# main.net
KiCad netlist of a schematic drawn in EAGLE
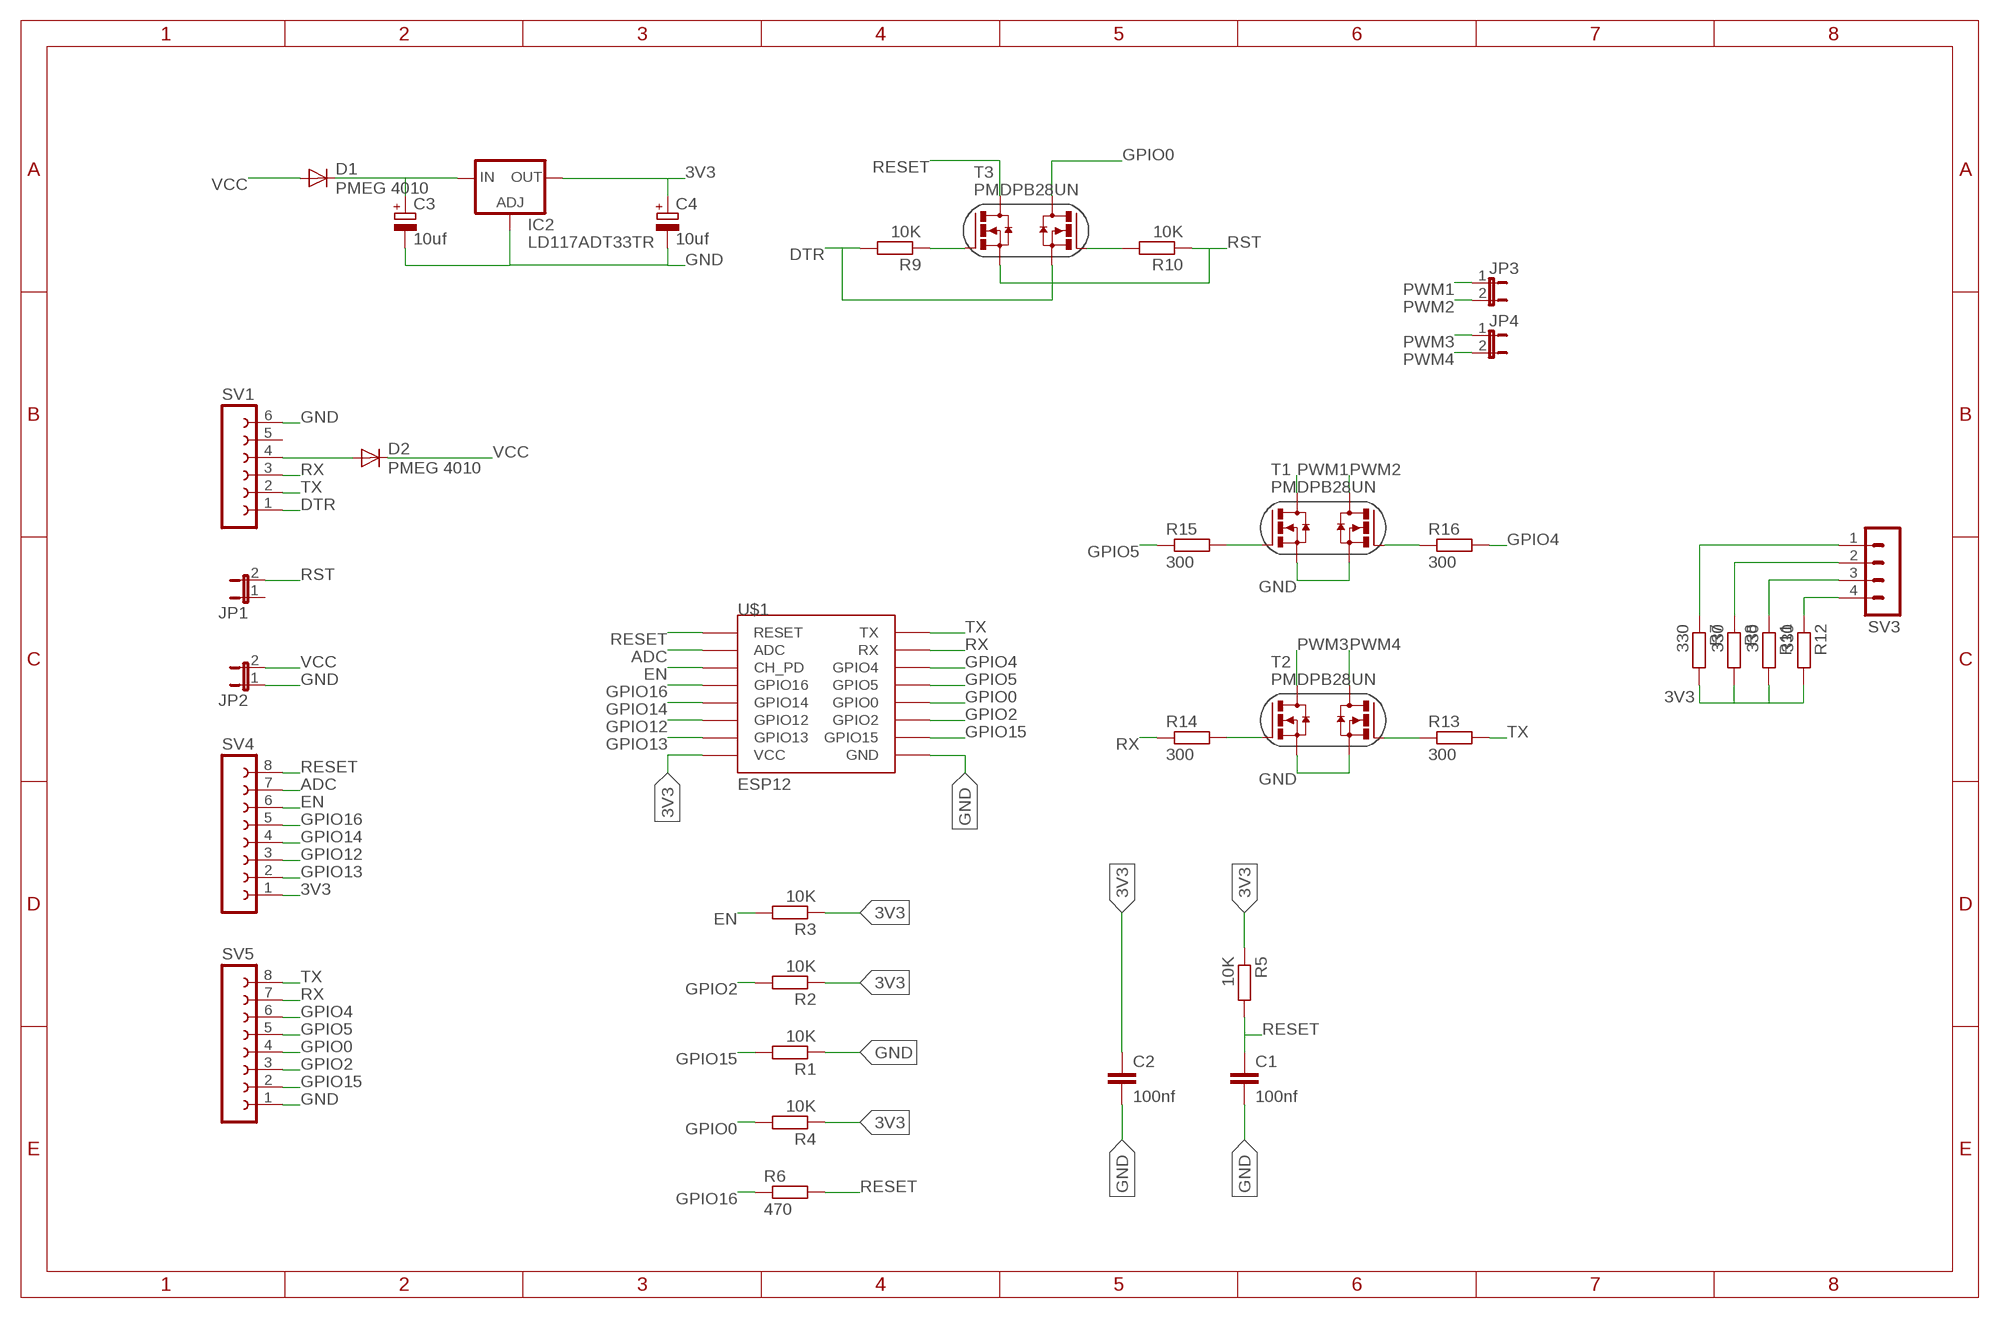
[diagram p0: schematic, sheet 1]

(export (version "E")
  (design (tool "Eeschema 10.0.6"))
  (components
    (comp (ref "C1")
      (value "100nf")
      (footprint "eagle-import:C0805K")
      (libsource (lib "eagle-import") (part "C-EUC0805K"))
    )
    (comp (ref "C2")
      (value "100nf")
      (footprint "eagle-import:C0805K")
      (libsource (lib "eagle-import") (part "C-EUC0805K"))
    )
    (comp (ref "C3")
      (value "10uf")
      (footprint "eagle-import:SMC_B")
      (libsource (lib "eagle-import") (part "CPOL-EUSMCB"))
    )
    (comp (ref "C4")
      (value "10uf")
      (footprint "eagle-import:SMC_B")
      (libsource (lib "eagle-import") (part "CPOL-EUSMCB"))
    )
    (comp (ref "D1")
      (value "PMEG 4010")
      (footprint "eagle-import:SOD-323")
      (libsource (lib "eagle-import") (part "DIODESOD"))
    )
    (comp (ref "D2")
      (value "PMEG 4010")
      (footprint "eagle-import:SOD-323")
      (libsource (lib "eagle-import") (part "DIODESOD"))
    )
    (comp (ref "IC2")
      (value "LD117ADT33TR")
      (footprint "eagle-import:DPACK")
      (libsource (lib "eagle-import") (part "LD117A?DT33TR"))
    )
    (comp (ref "JP1")
      (value "JUMPER-2PTH")
      (footprint "eagle-import:1X02")
      (libsource (lib "eagle-import") (part "JUMPER-2PTH"))
    )
    (comp (ref "JP2")
      (value "JUMPER-2PTH")
      (footprint "eagle-import:1X02")
      (libsource (lib "eagle-import") (part "JUMPER-2PTH"))
    )
    (comp (ref "JP3")
      (value "JUMPER-2PTH")
      (footprint "eagle-import:1X02")
      (libsource (lib "eagle-import") (part "JUMPER-2PTH"))
    )
    (comp (ref "JP4")
      (value "JUMPER-2PTH")
      (footprint "eagle-import:1X02")
      (libsource (lib "eagle-import") (part "JUMPER-2PTH"))
    )
    (comp (ref "R1")
      (value "10K")
      (footprint "eagle-import:R1206")
      (libsource (lib "eagle-import") (part "R-EU_R1206"))
    )
    (comp (ref "R2")
      (value "10K")
      (footprint "eagle-import:R1206")
      (libsource (lib "eagle-import") (part "R-EU_R1206"))
    )
    (comp (ref "R3")
      (value "10K")
      (footprint "eagle-import:R1206")
      (libsource (lib "eagle-import") (part "R-EU_R1206"))
    )
    (comp (ref "R4")
      (value "10K")
      (footprint "eagle-import:R1206")
      (libsource (lib "eagle-import") (part "R-EU_R1206"))
    )
    (comp (ref "R5")
      (value "10K")
      (footprint "eagle-import:R1206")
      (libsource (lib "eagle-import") (part "R-EU_R1206"))
    )
    (comp (ref "R6")
      (value "470")
      (footprint "eagle-import:R1206")
      (libsource (lib "eagle-import") (part "R-EU_R1206"))
    )
    (comp (ref "R7")
      (value "330")
      (footprint "eagle-import:R1206")
      (libsource (lib "eagle-import") (part "R-EU_R1206"))
    )
    (comp (ref "R8")
      (value "330")
      (footprint "eagle-import:R1206")
      (libsource (lib "eagle-import") (part "R-EU_R1206"))
    )
    (comp (ref "R9")
      (value "10K")
      (footprint "eagle-import:R1206")
      (libsource (lib "eagle-import") (part "R-EU_R1206"))
    )
    (comp (ref "R10")
      (value "10K")
      (footprint "eagle-import:R1206")
      (libsource (lib "eagle-import") (part "R-EU_R1206"))
    )
    (comp (ref "R11")
      (value "330")
      (footprint "eagle-import:R1206")
      (libsource (lib "eagle-import") (part "R-EU_R1206"))
    )
    (comp (ref "R12")
      (value "330")
      (footprint "eagle-import:R1206")
      (libsource (lib "eagle-import") (part "R-EU_R1206"))
    )
    (comp (ref "R13")
      (value "300")
      (footprint "eagle-import:R1206")
      (libsource (lib "eagle-import") (part "R-EU_R1206"))
    )
    (comp (ref "R14")
      (value "300")
      (footprint "eagle-import:R1206")
      (libsource (lib "eagle-import") (part "R-EU_R1206"))
    )
    (comp (ref "R15")
      (value "300")
      (footprint "eagle-import:R1206")
      (libsource (lib "eagle-import") (part "R-EU_R1206"))
    )
    (comp (ref "R16")
      (value "300")
      (footprint "eagle-import:R1206")
      (libsource (lib "eagle-import") (part "R-EU_R1206"))
    )
    (comp (ref "SV1")
      (value "FE06-1")
      (footprint "eagle-import:FE06")
      (libsource (lib "eagle-import") (part "FE06-1"))
    )
    (comp (ref "SV3")
      (value "MA04-1")
      (footprint "eagle-import:MA04-1")
      (libsource (lib "eagle-import") (part "MA04-1"))
    )
    (comp (ref "SV4")
      (value "FE08-1")
      (footprint "eagle-import:FE08")
      (libsource (lib "eagle-import") (part "FE08-1"))
    )
    (comp (ref "SV5")
      (value "FE08-1")
      (footprint "eagle-import:FE08")
      (libsource (lib "eagle-import") (part "FE08-1"))
    )
    (comp (ref "T1")
      (value "PMDPB28UN")
      (footprint "eagle-import:SOT1118")
      (libsource (lib "eagle-import") (part "PMDPB28UN"))
    )
    (comp (ref "T2")
      (value "PMDPB28UN")
      (footprint "eagle-import:SOT1118")
      (libsource (lib "eagle-import") (part "PMDPB28UN"))
    )
    (comp (ref "T3")
      (value "PMDPB28UN")
      (footprint "eagle-import:SOT1118")
      (libsource (lib "eagle-import") (part "PMDPB28UN"))
    )
    (comp (ref "U$1")
      (value "ESP12")
      (footprint "eagle-import:ESP12")
      (libsource (lib "eagle-import") (part "ESP12"))
    )
  )
  (nets
    (net (code "1") (name "/ADC") (class "Default")
      (node (ref "SV4") (pin "7") (pinfunction "7_7") (pintype "passive"))
      (node (ref "U$1") (pin "ADC") (pinfunction "ADC_ADC") (pintype "bidirectional"))
    )
    (net (code "2") (name "/DTR") (class "Default")
      (node (ref "R9") (pin "2") (pinfunction "2_2") (pintype "passive"))
      (node (ref "SV1") (pin "1") (pinfunction "1_1") (pintype "passive"))
      (node (ref "T3") (pin "S2") (pinfunction "S2_S2") (pintype "passive"))
    )
    (net (code "3") (name "/EN") (class "Default")
      (node (ref "R3") (pin "2") (pinfunction "2_2") (pintype "passive"))
      (node (ref "SV4") (pin "6") (pinfunction "6_6") (pintype "passive"))
      (node (ref "U$1") (pin "CH_PD") (pinfunction "CH_PD_CH_PD") (pintype "bidirectional"))
    )
    (net (code "4") (name "/GPIO0") (class "Default")
      (node (ref "R4") (pin "2") (pinfunction "2_2") (pintype "passive"))
      (node (ref "SV5") (pin "4") (pinfunction "4_4") (pintype "passive"))
      (node (ref "T3") (pin "D2") (pinfunction "D2_D2") (pintype "passive"))
      (node (ref "T3") (pin "D22") (pinfunction "D2_D22") (pintype "passive"))
      (node (ref "U$1") (pin "GPIO0") (pinfunction "GPIO0_GPIO0") (pintype "bidirectional"))
    )
    (net (code "5") (name "/GPIO2") (class "Default")
      (node (ref "R2") (pin "2") (pinfunction "2_2") (pintype "passive"))
      (node (ref "SV5") (pin "3") (pinfunction "3_3") (pintype "passive"))
      (node (ref "U$1") (pin "GPIO2") (pinfunction "GPIO2_GPIO2") (pintype "bidirectional"))
    )
    (net (code "6") (name "/GPIO4") (class "Default")
      (node (ref "R16") (pin "2") (pinfunction "2_2") (pintype "passive"))
      (node (ref "SV5") (pin "6") (pinfunction "6_6") (pintype "passive"))
      (node (ref "U$1") (pin "GPIO4") (pinfunction "GPIO4_GPIO4") (pintype "bidirectional"))
    )
    (net (code "7") (name "/GPIO5") (class "Default")
      (node (ref "R15") (pin "1") (pinfunction "1_1") (pintype "passive"))
      (node (ref "SV5") (pin "5") (pinfunction "5_5") (pintype "passive"))
      (node (ref "U$1") (pin "GPIO5") (pinfunction "GPIO5_GPIO5") (pintype "bidirectional"))
    )
    (net (code "8") (name "/GPIO12") (class "Default")
      (node (ref "SV4") (pin "3") (pinfunction "3_3") (pintype "passive"))
      (node (ref "U$1") (pin "GPIO12") (pinfunction "GPIO12_GPIO12") (pintype "bidirectional"))
    )
    (net (code "9") (name "/GPIO13") (class "Default")
      (node (ref "SV4") (pin "2") (pinfunction "2_2") (pintype "passive"))
      (node (ref "U$1") (pin "GPIO13") (pinfunction "GPIO13_GPIO13") (pintype "bidirectional"))
    )
    (net (code "10") (name "/GPIO14") (class "Default")
      (node (ref "SV4") (pin "4") (pinfunction "4_4") (pintype "passive"))
      (node (ref "U$1") (pin "GPIO14") (pinfunction "GPIO14_GPIO14") (pintype "bidirectional"))
    )
    (net (code "11") (name "/GPIO15") (class "Default")
      (node (ref "R1") (pin "2") (pinfunction "2_2") (pintype "passive"))
      (node (ref "SV5") (pin "2") (pinfunction "2_2") (pintype "passive"))
      (node (ref "U$1") (pin "GPIO15") (pinfunction "GPIO15_GPIO15") (pintype "bidirectional"))
    )
    (net (code "12") (name "/GPIO16") (class "Default")
      (node (ref "R6") (pin "1") (pinfunction "1_1") (pintype "passive"))
      (node (ref "SV4") (pin "5") (pinfunction "5_5") (pintype "passive"))
      (node (ref "U$1") (pin "GPIO16") (pinfunction "GPIO16_GPIO16") (pintype "bidirectional"))
    )
    (net (code "13") (name "/PWM1") (class "Default")
      (node (ref "JP3") (pin "1") (pinfunction "1_1") (pintype "passive"))
      (node (ref "T1") (pin "D1") (pinfunction "D1_D1") (pintype "passive"))
      (node (ref "T1") (pin "D11") (pinfunction "D1_D11") (pintype "passive"))
    )
    (net (code "14") (name "/PWM2") (class "Default")
      (node (ref "JP3") (pin "2") (pinfunction "2_2") (pintype "passive"))
      (node (ref "T1") (pin "D2") (pinfunction "D2_D2") (pintype "passive"))
      (node (ref "T1") (pin "D22") (pinfunction "D2_D22") (pintype "passive"))
    )
    (net (code "15") (name "/PWM3") (class "Default")
      (node (ref "JP4") (pin "1") (pinfunction "1_1") (pintype "passive"))
      (node (ref "T2") (pin "D1") (pinfunction "D1_D1") (pintype "passive"))
      (node (ref "T2") (pin "D11") (pinfunction "D1_D11") (pintype "passive"))
    )
    (net (code "16") (name "/PWM4") (class "Default")
      (node (ref "JP4") (pin "2") (pinfunction "2_2") (pintype "passive"))
      (node (ref "T2") (pin "D2") (pinfunction "D2_D2") (pintype "passive"))
      (node (ref "T2") (pin "D22") (pinfunction "D2_D22") (pintype "passive"))
    )
    (net (code "17") (name "/RESET") (class "Default")
      (node (ref "C1") (pin "1") (pinfunction "1_1") (pintype "passive"))
      (node (ref "R5") (pin "2") (pinfunction "2_2") (pintype "passive"))
      (node (ref "R6") (pin "2") (pinfunction "2_2") (pintype "passive"))
      (node (ref "SV4") (pin "8") (pinfunction "8_8") (pintype "passive"))
      (node (ref "T3") (pin "D1") (pinfunction "D1_D1") (pintype "passive"))
      (node (ref "T3") (pin "D11") (pinfunction "D1_D11") (pintype "passive"))
      (node (ref "U$1") (pin "RESET") (pinfunction "RESET_RESET") (pintype "bidirectional"))
    )
    (net (code "18") (name "/RST") (class "Default")
      (node (ref "JP1") (pin "2") (pinfunction "2_2") (pintype "passive"))
      (node (ref "R10") (pin "1") (pinfunction "1_1") (pintype "passive"))
      (node (ref "T3") (pin "S1") (pinfunction "S1_S1") (pintype "passive"))
    )
    (net (code "19") (name "/RX") (class "Default")
      (node (ref "R14") (pin "1") (pinfunction "1_1") (pintype "passive"))
      (node (ref "SV1") (pin "3") (pinfunction "3_3") (pintype "passive"))
      (node (ref "SV5") (pin "7") (pinfunction "7_7") (pintype "passive"))
      (node (ref "U$1") (pin "RX") (pinfunction "RX_RX") (pintype "bidirectional"))
    )
    (net (code "20") (name "/TX") (class "Default")
      (node (ref "R13") (pin "2") (pinfunction "2_2") (pintype "passive"))
      (node (ref "SV1") (pin "2") (pinfunction "2_2") (pintype "passive"))
      (node (ref "SV5") (pin "8") (pinfunction "8_8") (pintype "passive"))
      (node (ref "U$1") (pin "TX") (pinfunction "TX_TX") (pintype "bidirectional"))
    )
    (net (code "21") (name "/VCC") (class "Default")
      (node (ref "C3") (pin "+") (pinfunction "+_+") (pintype "passive"))
      (node (ref "D1") (pin "1") (pinfunction "C_1") (pintype "passive"))
      (node (ref "D1") (pin "2") (pinfunction "A_2") (pintype "passive"))
      (node (ref "D2") (pin "1") (pinfunction "C_1") (pintype "passive"))
      (node (ref "IC2") (pin "3") (pinfunction "IN_3") (pintype "input"))
      (node (ref "JP2") (pin "2") (pinfunction "2_2") (pintype "passive"))
    )
    (net (code "22") (name "3V3") (class "Default")
      (node (ref "C2") (pin "1") (pinfunction "1_1") (pintype "passive"))
      (node (ref "C4") (pin "+") (pinfunction "+_+") (pintype "passive"))
      (node (ref "IC2") (pin "4") (pinfunction "OUT_4") (pintype "passive"))
      (node (ref "R11") (pin "2") (pinfunction "2_2") (pintype "passive"))
      (node (ref "R12") (pin "2") (pinfunction "2_2") (pintype "passive"))
      (node (ref "R2") (pin "1") (pinfunction "1_1") (pintype "passive"))
      (node (ref "R3") (pin "1") (pinfunction "1_1") (pintype "passive"))
      (node (ref "R4") (pin "1") (pinfunction "1_1") (pintype "passive"))
      (node (ref "R5") (pin "1") (pinfunction "1_1") (pintype "passive"))
      (node (ref "R7") (pin "2") (pinfunction "2_2") (pintype "passive"))
      (node (ref "R8") (pin "2") (pinfunction "2_2") (pintype "passive"))
      (node (ref "SV4") (pin "1") (pinfunction "1_1") (pintype "passive"))
      (node (ref "U$1") (pin "VCC") (pinfunction "VCC_VCC") (pintype "bidirectional"))
    )
    (net (code "23") (name "GND") (class "Default")
      (node (ref "C1") (pin "2") (pinfunction "2_2") (pintype "passive"))
      (node (ref "C2") (pin "2") (pinfunction "2_2") (pintype "passive"))
      (node (ref "C3") (pin "-") (pinfunction "-_-") (pintype "passive"))
      (node (ref "C4") (pin "-") (pinfunction "-_-") (pintype "passive"))
      (node (ref "IC2") (pin "1") (pinfunction "ADJ_1") (pintype "input"))
      (node (ref "JP2") (pin "1") (pinfunction "1_1") (pintype "passive"))
      (node (ref "R1") (pin "1") (pinfunction "1_1") (pintype "passive"))
      (node (ref "SV1") (pin "6") (pinfunction "6_6") (pintype "passive"))
      (node (ref "SV5") (pin "1") (pinfunction "1_1") (pintype "passive"))
      (node (ref "T1") (pin "S1") (pinfunction "S1_S1") (pintype "passive"))
      (node (ref "T1") (pin "S2") (pinfunction "S2_S2") (pintype "passive"))
      (node (ref "T2") (pin "S1") (pinfunction "S1_S1") (pintype "passive"))
      (node (ref "T2") (pin "S2") (pinfunction "S2_S2") (pintype "passive"))
      (node (ref "U$1") (pin "GND") (pinfunction "GND_GND") (pintype "bidirectional"))
    )
    (net (code "24") (name "Net-(D2-A)") (class "Default")
      (node (ref "D2") (pin "2") (pinfunction "A_2") (pintype "passive"))
      (node (ref "SV1") (pin "4") (pinfunction "4_4") (pintype "passive"))
    )
    (net (code "25") (name "Net-(R7-Pad1)") (class "Default")
      (node (ref "R7") (pin "1") (pinfunction "1_1") (pintype "passive"))
      (node (ref "SV3") (pin "1") (pinfunction "1_1") (pintype "passive"))
    )
    (net (code "26") (name "Net-(R8-Pad1)") (class "Default")
      (node (ref "R8") (pin "1") (pinfunction "1_1") (pintype "passive"))
      (node (ref "SV3") (pin "2") (pinfunction "2_2") (pintype "passive"))
    )
    (net (code "27") (name "Net-(R9-Pad1)") (class "Default")
      (node (ref "R9") (pin "1") (pinfunction "1_1") (pintype "passive"))
      (node (ref "T3") (pin "G1") (pinfunction "G1_G1") (pintype "passive"))
    )
    (net (code "28") (name "Net-(R10-Pad2)") (class "Default")
      (node (ref "R10") (pin "2") (pinfunction "2_2") (pintype "passive"))
      (node (ref "T3") (pin "G2") (pinfunction "G2_G2") (pintype "passive"))
    )
    (net (code "29") (name "Net-(R11-Pad1)") (class "Default")
      (node (ref "R11") (pin "1") (pinfunction "1_1") (pintype "passive"))
      (node (ref "SV3") (pin "3") (pinfunction "3_3") (pintype "passive"))
    )
    (net (code "30") (name "Net-(R12-Pad1)") (class "Default")
      (node (ref "R12") (pin "1") (pinfunction "1_1") (pintype "passive"))
      (node (ref "SV3") (pin "4") (pinfunction "4_4") (pintype "passive"))
    )
    (net (code "31") (name "Net-(R13-Pad1)") (class "Default")
      (node (ref "R13") (pin "1") (pinfunction "1_1") (pintype "passive"))
      (node (ref "T2") (pin "G2") (pinfunction "G2_G2") (pintype "passive"))
    )
    (net (code "32") (name "Net-(R14-Pad2)") (class "Default")
      (node (ref "R14") (pin "2") (pinfunction "2_2") (pintype "passive"))
      (node (ref "T2") (pin "G1") (pinfunction "G1_G1") (pintype "passive"))
    )
    (net (code "33") (name "Net-(R15-Pad2)") (class "Default")
      (node (ref "R15") (pin "2") (pinfunction "2_2") (pintype "passive"))
      (node (ref "T1") (pin "G1") (pinfunction "G1_G1") (pintype "passive"))
    )
    (net (code "34") (name "Net-(R16-Pad1)") (class "Default")
      (node (ref "R16") (pin "1") (pinfunction "1_1") (pintype "passive"))
      (node (ref "T1") (pin "G2") (pinfunction "G2_G2") (pintype "passive"))
    )
    (net (code "35") (name "unconnected-(JP1-Pad1)") (class "Default")
      (node (ref "JP1") (pin "1") (pinfunction "1_1") (pintype "passive"))
    )
    (net (code "36") (name "unconnected-(SV1-Pad5)") (class "Default")
      (node (ref "SV1") (pin "5") (pinfunction "5_5") (pintype "passive"))
    )
  )
)
